# blinds-shield.net
KiCad netlist of a schematic drawn in EAGLE
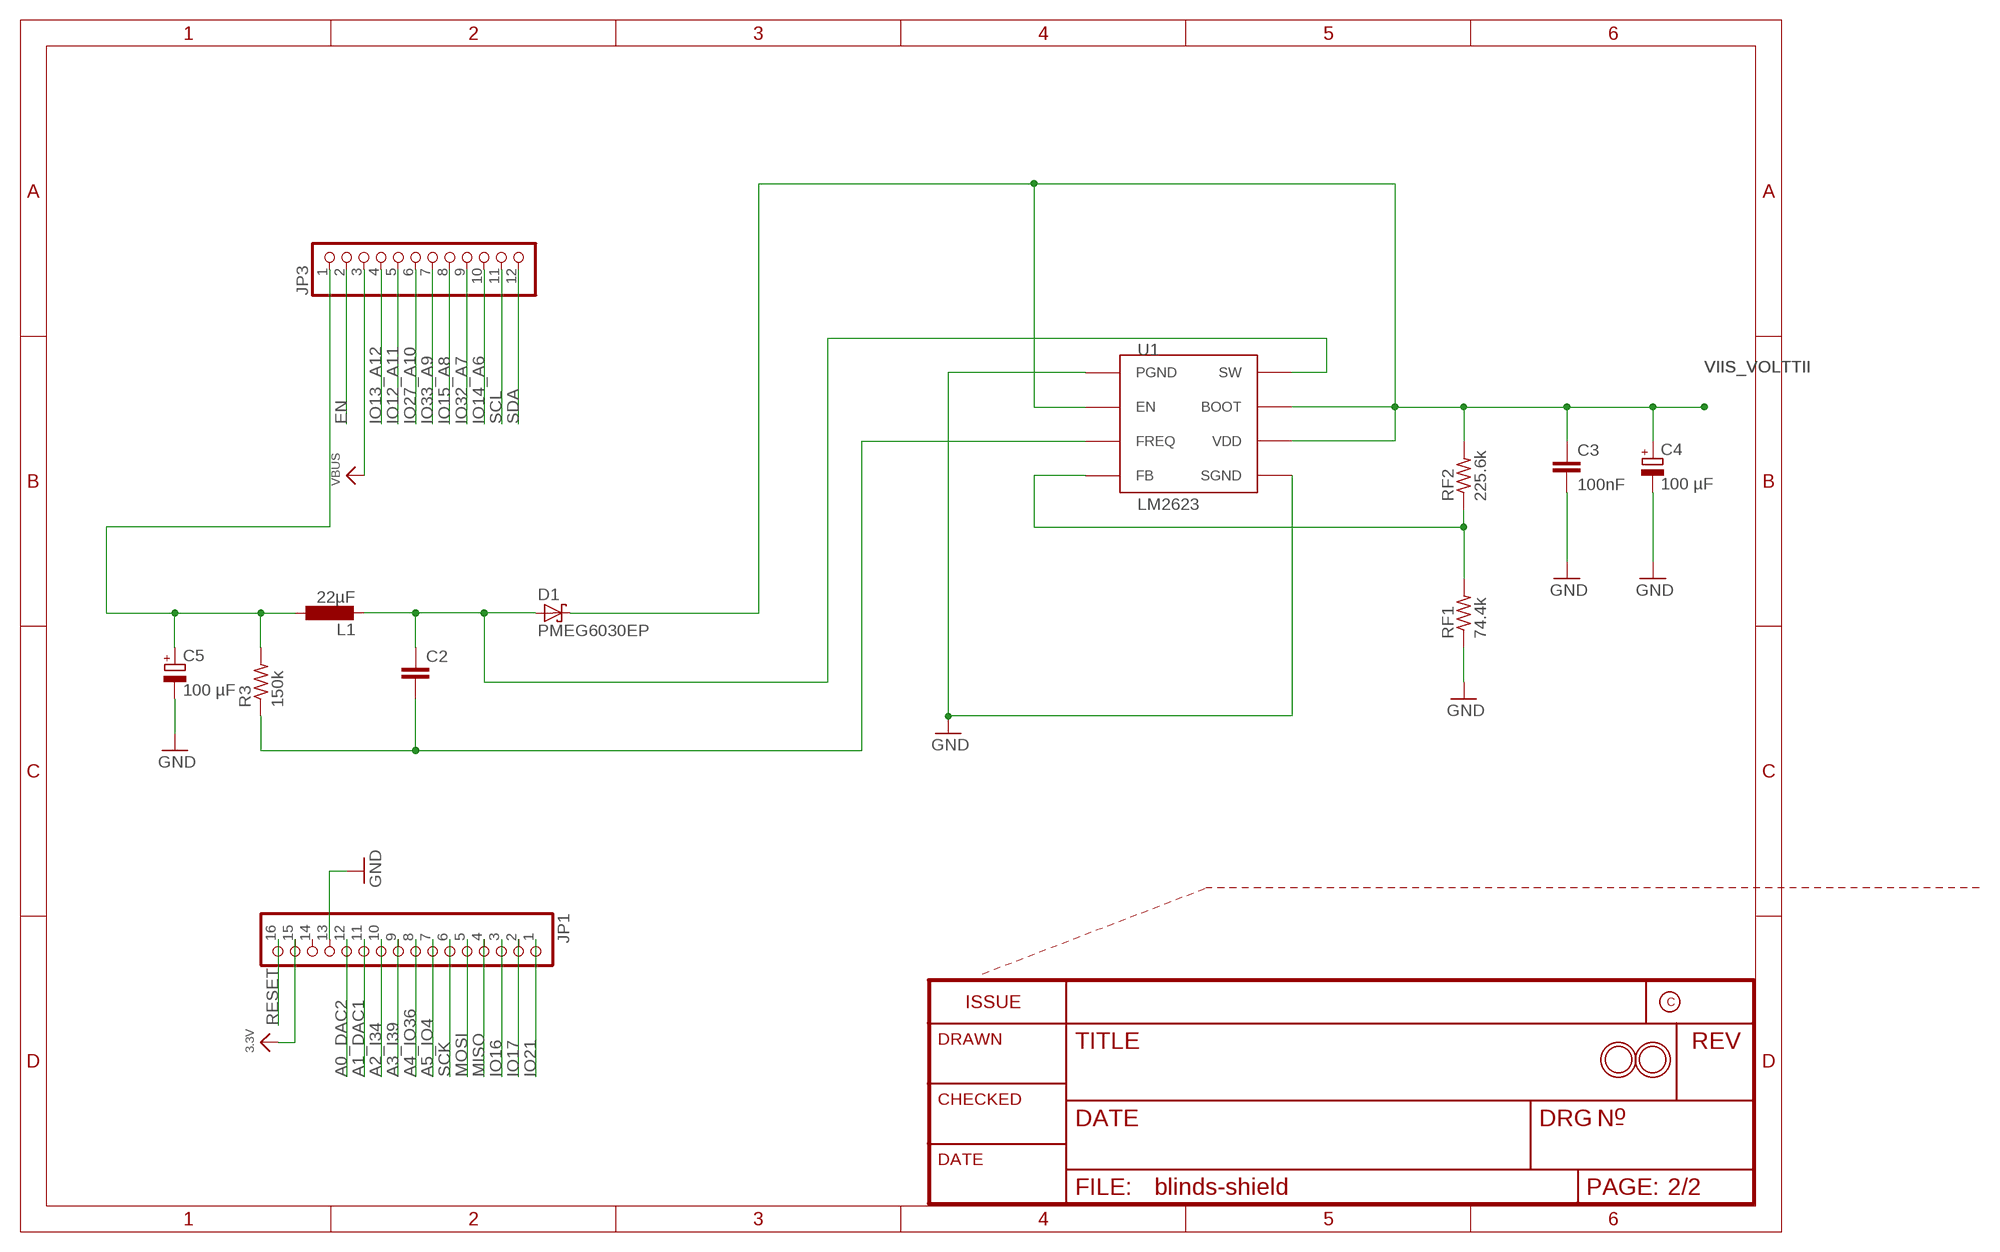
[diagram p0: schematic, sheet 2]

(export (version "E")
  (design (tool "Eeschema 10.0.6"))
  (components
    (comp (ref "C2")
      (value "C-EU025-060X050")
      (footprint "eagle-import:C025-060X050")
      (libsource (lib "eagle-import") (part "C-EU025-060X050"))
    )
    (comp (ref "C3")
      (value "100nF")
      (footprint "eagle-import:C025-060X050")
      (libsource (lib "eagle-import") (part "C-EU025-060X050"))
    )
    (comp (ref "C4")
      (value "100 µF")
      (footprint "eagle-import:085CS_1AR")
      (libsource (lib "eagle-import") (part "CPOL-EU085CS-1AR"))
    )
    (comp (ref "C5")
      (value "100 µF")
      (footprint "eagle-import:085CS_1AR")
      (libsource (lib "eagle-import") (part "CPOL-EU085CS-1AR"))
    )
    (comp (ref "D1")
      (value "PMEG6030EP")
      (footprint "eagle-import:SOD128")
      (libsource (lib "eagle-import") (part "PMEG6030EP"))
    )
    (comp (ref "JP1")
      (value "HEADER-1X16_MIN")
      (footprint "eagle-import:1X16_ROUND_MIN")
      (libsource (lib "eagle-import") (part "HEADER-1X16_MIN"))
    )
    (comp (ref "JP3")
      (value "HEADER-1X12_MIN")
      (footprint "eagle-import:1X12_ROUND_MIN")
      (libsource (lib "eagle-import") (part "HEADER-1X12_MIN"))
    )
    (comp (ref "L1")
      (value "22µF")
      (footprint "eagle-import:L5650M")
      (libsource (lib "eagle-import") (part "L-EUL5650M"))
    )
    (comp (ref "R3")
      (value "150k")
      (footprint "eagle-import:R5025")
      (libsource (lib "eagle-import") (part "R-US_R5025"))
    )
    (comp (ref "RF1")
      (value "74.4k")
      (footprint "eagle-import:R5025")
      (libsource (lib "eagle-import") (part "R-US_R5025"))
    )
    (comp (ref "RF2")
      (value "225.6k")
      (footprint "eagle-import:R5025")
      (libsource (lib "eagle-import") (part "R-US_R5025"))
    )
    (comp (ref "U$31")
      (value "MOUNTINGHOLE2.5")
      (footprint "eagle-import:MOUNTINGHOLE_2.5_PLATED")
      (libsource (lib "eagle-import") (part "MOUNTINGHOLE2.5"))
    )
    (comp (ref "U$32")
      (value "MOUNTINGHOLE2.5")
      (footprint "eagle-import:MOUNTINGHOLE_2.5_PLATED")
      (libsource (lib "eagle-import") (part "MOUNTINGHOLE2.5"))
    )
    (comp (ref "U1")
      (value "LM2623")
      (footprint "eagle-import:VSSOP8")
      (libsource (lib "eagle-import") (part "LM2623"))
    )
  )
  (nets
    (net (code "1") (name "3.3V") (class "Default")
      (node (ref "JP1") (pin "15") (pinfunction "15_15") (pintype "passive"))
    )
    (net (code "2") (name "A0_DAC2") (class "Default")
      (node (ref "JP1") (pin "12") (pinfunction "12_12") (pintype "passive"))
    )
    (net (code "3") (name "A1_DAC1") (class "Default")
      (node (ref "JP1") (pin "11") (pinfunction "11_11") (pintype "passive"))
    )
    (net (code "4") (name "A2_I34") (class "Default")
      (node (ref "JP1") (pin "10") (pinfunction "10_10") (pintype "passive"))
    )
    (net (code "5") (name "A3_I39") (class "Default")
      (node (ref "JP1") (pin "9") (pinfunction "9_9") (pintype "passive"))
    )
    (net (code "6") (name "A4_IO36") (class "Default")
      (node (ref "JP1") (pin "8") (pinfunction "8_8") (pintype "passive"))
    )
    (net (code "7") (name "A5_IO4") (class "Default")
      (node (ref "JP1") (pin "7") (pinfunction "7_7") (pintype "passive"))
    )
    (net (code "8") (name "EN") (class "Default")
      (node (ref "JP3") (pin "2") (pinfunction "2_2") (pintype "passive"))
    )
    (net (code "9") (name "GND") (class "Default")
      (node (ref "C3") (pin "2") (pinfunction "2_2") (pintype "passive"))
      (node (ref "C4") (pin "-") (pinfunction "-_-") (pintype "passive"))
      (node (ref "C5") (pin "-") (pinfunction "-_-") (pintype "passive"))
      (node (ref "JP1") (pin "13") (pinfunction "13_13") (pintype "passive"))
      (node (ref "RF1") (pin "1") (pinfunction "1_1") (pintype "passive"))
      (node (ref "U1") (pin "PGND") (pinfunction "PGND_PGND") (pintype "bidirectional"))
      (node (ref "U1") (pin "SGND") (pinfunction "SGND_SGND") (pintype "bidirectional"))
    )
    (net (code "10") (name "IO12_A11") (class "Default")
      (node (ref "JP3") (pin "5") (pinfunction "5_5") (pintype "passive"))
    )
    (net (code "11") (name "IO13_A12") (class "Default")
      (node (ref "JP3") (pin "4") (pinfunction "4_4") (pintype "passive"))
    )
    (net (code "12") (name "IO14_A6") (class "Default")
      (node (ref "JP3") (pin "10") (pinfunction "10_10") (pintype "passive"))
    )
    (net (code "13") (name "IO15_A8") (class "Default")
      (node (ref "JP3") (pin "8") (pinfunction "8_8") (pintype "passive"))
    )
    (net (code "14") (name "IO16") (class "Default")
      (node (ref "JP1") (pin "3") (pinfunction "3_3") (pintype "passive"))
    )
    (net (code "15") (name "IO17") (class "Default")
      (node (ref "JP1") (pin "2") (pinfunction "2_2") (pintype "passive"))
    )
    (net (code "16") (name "IO21") (class "Default")
      (node (ref "JP1") (pin "1") (pinfunction "1_1") (pintype "passive"))
    )
    (net (code "17") (name "IO27_A10") (class "Default")
      (node (ref "JP3") (pin "6") (pinfunction "6_6") (pintype "passive"))
    )
    (net (code "18") (name "IO32_A7") (class "Default")
      (node (ref "JP3") (pin "9") (pinfunction "9_9") (pintype "passive"))
    )
    (net (code "19") (name "IO33_A9") (class "Default")
      (node (ref "JP3") (pin "7") (pinfunction "7_7") (pintype "passive"))
    )
    (net (code "20") (name "MISO") (class "Default")
      (node (ref "JP1") (pin "4") (pinfunction "4_4") (pintype "passive"))
    )
    (net (code "21") (name "MOSI") (class "Default")
      (node (ref "JP1") (pin "5") (pinfunction "5_5") (pintype "passive"))
    )
    (net (code "22") (name "Net-(C2-Pad2)") (class "Default")
      (node (ref "C2") (pin "2") (pinfunction "2_2") (pintype "passive"))
      (node (ref "R3") (pin "1") (pinfunction "1_1") (pintype "passive"))
      (node (ref "U1") (pin "FREQ") (pinfunction "FREQ_FREQ") (pintype "bidirectional"))
    )
    (net (code "23") (name "Net-(C5-Pad+)") (class "Default")
      (node (ref "C5") (pin "+") (pinfunction "+_+") (pintype "passive"))
      (node (ref "JP3") (pin "1") (pinfunction "1_1") (pintype "passive"))
      (node (ref "L1") (pin "1") (pinfunction "1_1") (pintype "passive"))
      (node (ref "R3") (pin "2") (pinfunction "2_2") (pintype "passive"))
    )
    (net (code "24") (name "Net-(D1-A)") (class "Default")
      (node (ref "C2") (pin "1") (pinfunction "1_1") (pintype "passive"))
      (node (ref "D1") (pin "2") (pinfunction "A_2") (pintype "passive"))
      (node (ref "L1") (pin "2") (pinfunction "2_2") (pintype "passive"))
      (node (ref "U1") (pin "SW") (pinfunction "SW_SW") (pintype "bidirectional"))
    )
    (net (code "25") (name "Net-(RF1-Pad2)") (class "Default")
      (node (ref "RF1") (pin "2") (pinfunction "2_2") (pintype "passive"))
      (node (ref "RF2") (pin "1") (pinfunction "1_1") (pintype "passive"))
      (node (ref "U1") (pin "FB") (pinfunction "FB_FB") (pintype "bidirectional"))
    )
    (net (code "26") (name "RESET") (class "Default")
      (node (ref "JP1") (pin "16") (pinfunction "16_16") (pintype "passive"))
    )
    (net (code "27") (name "SCK") (class "Default")
      (node (ref "JP1") (pin "6") (pinfunction "6_6") (pintype "passive"))
    )
    (net (code "28") (name "SCL") (class "Default")
      (node (ref "JP3") (pin "11") (pinfunction "11_11") (pintype "passive"))
    )
    (net (code "29") (name "SDA") (class "Default")
      (node (ref "JP3") (pin "12") (pinfunction "12_12") (pintype "passive"))
    )
    (net (code "30") (name "VBUS") (class "Default")
      (node (ref "JP3") (pin "3") (pinfunction "3_3") (pintype "passive"))
    )
    (net (code "31") (name "VIIS_VOLTTII") (class "Default")
      (node (ref "C3") (pin "1") (pinfunction "1_1") (pintype "passive"))
      (node (ref "C4") (pin "+") (pinfunction "+_+") (pintype "passive"))
      (node (ref "D1") (pin "1") (pinfunction "K_1") (pintype "passive"))
      (node (ref "RF2") (pin "2") (pinfunction "2_2") (pintype "passive"))
      (node (ref "U1") (pin "BOOT") (pinfunction "BOOT_BOOT") (pintype "bidirectional"))
      (node (ref "U1") (pin "EN") (pinfunction "EN_EN") (pintype "bidirectional"))
      (node (ref "U1") (pin "VDD") (pinfunction "VDD_VDD") (pintype "bidirectional"))
    )
    (net (code "32") (name "unconnected-(JP1-Pad14)") (class "Default")
      (node (ref "JP1") (pin "14") (pinfunction "14_14") (pintype "passive"))
    )
  )
)
